# SainSmartTFT.net
KiCad netlist of a schematic drawn in Altium Designer
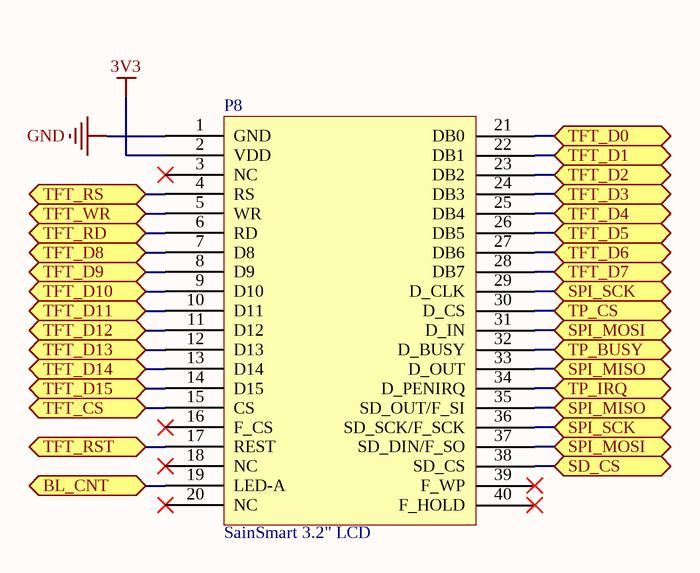
[diagram p0: SainSmartTFT.SchDoc]

(export (version "E")
  (design (tool "Eeschema 10.0.6"))
  (components
    (comp (ref "P8")
      (value "SainSmart 3.2\" LCD")
      (footprint "HDR2x20")
      (libsource (lib "BrewBit") (part "SainSmart 3.2{dblquote} LCD"))
    )
  )
  (nets
    (net (code "1") (name "/BL_CNT") (class "Default")
      (node (ref "P8") (pin "19") (pinfunction "LED-A_19") (pintype "passive"))
    )
    (net (code "2") (name "/SD_CS") (class "Default")
      (node (ref "P8") (pin "38") (pinfunction "SD_CS_38") (pintype "passive"))
    )
    (net (code "3") (name "/SPI_MISO") (class "Default")
      (node (ref "P8") (pin "33") (pinfunction "D_OUT_33") (pintype "passive"))
      (node (ref "P8") (pin "35") (pinfunction "SD_OUT/F_SI_35") (pintype "passive"))
    )
    (net (code "4") (name "/SPI_MOSI") (class "Default")
      (node (ref "P8") (pin "31") (pinfunction "D_IN_31") (pintype "passive"))
      (node (ref "P8") (pin "37") (pinfunction "SD_DIN/F_SO_37") (pintype "passive"))
    )
    (net (code "5") (name "/SPI_SCK") (class "Default")
      (node (ref "P8") (pin "29") (pinfunction "D_CLK_29") (pintype "passive"))
      (node (ref "P8") (pin "36") (pinfunction "SD_SCK/F_SCK_36") (pintype "passive"))
    )
    (net (code "6") (name "/TFT_CS") (class "Default")
      (node (ref "P8") (pin "15") (pinfunction "CS_15") (pintype "passive"))
    )
    (net (code "7") (name "/TFT_D0") (class "Default")
      (node (ref "P8") (pin "21") (pinfunction "DB0_21") (pintype "passive"))
    )
    (net (code "8") (name "/TFT_D1") (class "Default")
      (node (ref "P8") (pin "22") (pinfunction "DB1_22") (pintype "passive"))
    )
    (net (code "9") (name "/TFT_D2") (class "Default")
      (node (ref "P8") (pin "23") (pinfunction "DB2_23") (pintype "passive"))
    )
    (net (code "10") (name "/TFT_D3") (class "Default")
      (node (ref "P8") (pin "24") (pinfunction "DB3_24") (pintype "passive"))
    )
    (net (code "11") (name "/TFT_D4") (class "Default")
      (node (ref "P8") (pin "25") (pinfunction "DB4_25") (pintype "passive"))
    )
    (net (code "12") (name "/TFT_D5") (class "Default")
      (node (ref "P8") (pin "26") (pinfunction "DB5_26") (pintype "passive"))
    )
    (net (code "13") (name "/TFT_D6") (class "Default")
      (node (ref "P8") (pin "27") (pinfunction "DB6_27") (pintype "passive"))
    )
    (net (code "14") (name "/TFT_D7") (class "Default")
      (node (ref "P8") (pin "28") (pinfunction "DB7_28") (pintype "passive"))
    )
    (net (code "15") (name "/TFT_D8") (class "Default")
      (node (ref "P8") (pin "7") (pinfunction "D8_7") (pintype "passive"))
    )
    (net (code "16") (name "/TFT_D9") (class "Default")
      (node (ref "P8") (pin "8") (pinfunction "D9_8") (pintype "passive"))
    )
    (net (code "17") (name "/TFT_D10") (class "Default")
      (node (ref "P8") (pin "9") (pinfunction "D10_9") (pintype "passive"))
    )
    (net (code "18") (name "/TFT_D11") (class "Default")
      (node (ref "P8") (pin "10") (pinfunction "D11_10") (pintype "passive"))
    )
    (net (code "19") (name "/TFT_D12") (class "Default")
      (node (ref "P8") (pin "11") (pinfunction "D12_11") (pintype "passive"))
    )
    (net (code "20") (name "/TFT_D13") (class "Default")
      (node (ref "P8") (pin "12") (pinfunction "D13_12") (pintype "passive"))
    )
    (net (code "21") (name "/TFT_D14") (class "Default")
      (node (ref "P8") (pin "13") (pinfunction "D14_13") (pintype "passive"))
    )
    (net (code "22") (name "/TFT_D15") (class "Default")
      (node (ref "P8") (pin "14") (pinfunction "D15_14") (pintype "passive"))
    )
    (net (code "23") (name "/TFT_RD") (class "Default")
      (node (ref "P8") (pin "6") (pinfunction "RD_6") (pintype "passive"))
    )
    (net (code "24") (name "/TFT_RS") (class "Default")
      (node (ref "P8") (pin "4") (pinfunction "RS_4") (pintype "passive"))
    )
    (net (code "25") (name "/TFT_RST") (class "Default")
      (node (ref "P8") (pin "17") (pinfunction "REST_17") (pintype "passive"))
    )
    (net (code "26") (name "/TFT_WR") (class "Default")
      (node (ref "P8") (pin "5") (pinfunction "WR_5") (pintype "passive"))
    )
    (net (code "27") (name "/TP_BUSY") (class "Default")
      (node (ref "P8") (pin "32") (pinfunction "D_BUSY_32") (pintype "passive"))
    )
    (net (code "28") (name "/TP_CS") (class "Default")
      (node (ref "P8") (pin "30") (pinfunction "D_CS_30") (pintype "passive"))
    )
    (net (code "29") (name "/TP_IRQ") (class "Default")
      (node (ref "P8") (pin "34") (pinfunction "D_PENIRQ_34") (pintype "passive"))
    )
    (net (code "30") (name "3V3") (class "Default")
      (node (ref "P8") (pin "2") (pinfunction "VDD_2") (pintype "passive"))
    )
    (net (code "31") (name "GND") (class "Default")
      (node (ref "P8") (pin "1") (pinfunction "GND_1") (pintype "passive"))
    )
    (net (code "32") (name "unconnected-(P8-F_CS-Pad16)") (class "Default")
      (node (ref "P8") (pin "16") (pinfunction "F_CS_16") (pintype "passive+no_connect"))
    )
    (net (code "33") (name "unconnected-(P8-F_HOLD-Pad40)") (class "Default")
      (node (ref "P8") (pin "40") (pinfunction "F_HOLD_40") (pintype "passive+no_connect"))
    )
    (net (code "34") (name "unconnected-(P8-F_WP-Pad39)") (class "Default")
      (node (ref "P8") (pin "39") (pinfunction "F_WP_39") (pintype "passive+no_connect"))
    )
    (net (code "35") (name "unconnected-(P8-NC-Pad3)") (class "Default")
      (node (ref "P8") (pin "3") (pinfunction "NC_3") (pintype "passive+no_connect"))
    )
    (net (code "36") (name "unconnected-(P8-NC-Pad18)") (class "Default")
      (node (ref "P8") (pin "18") (pinfunction "NC_18") (pintype "passive+no_connect"))
    )
    (net (code "37") (name "unconnected-(P8-NC-Pad20)") (class "Default")
      (node (ref "P8") (pin "20") (pinfunction "NC_20") (pintype "passive+no_connect"))
    )
  )
)
